# stamp-fixed-mk-4_2.net
KiCad netlist of a schematic drawn in EAGLE
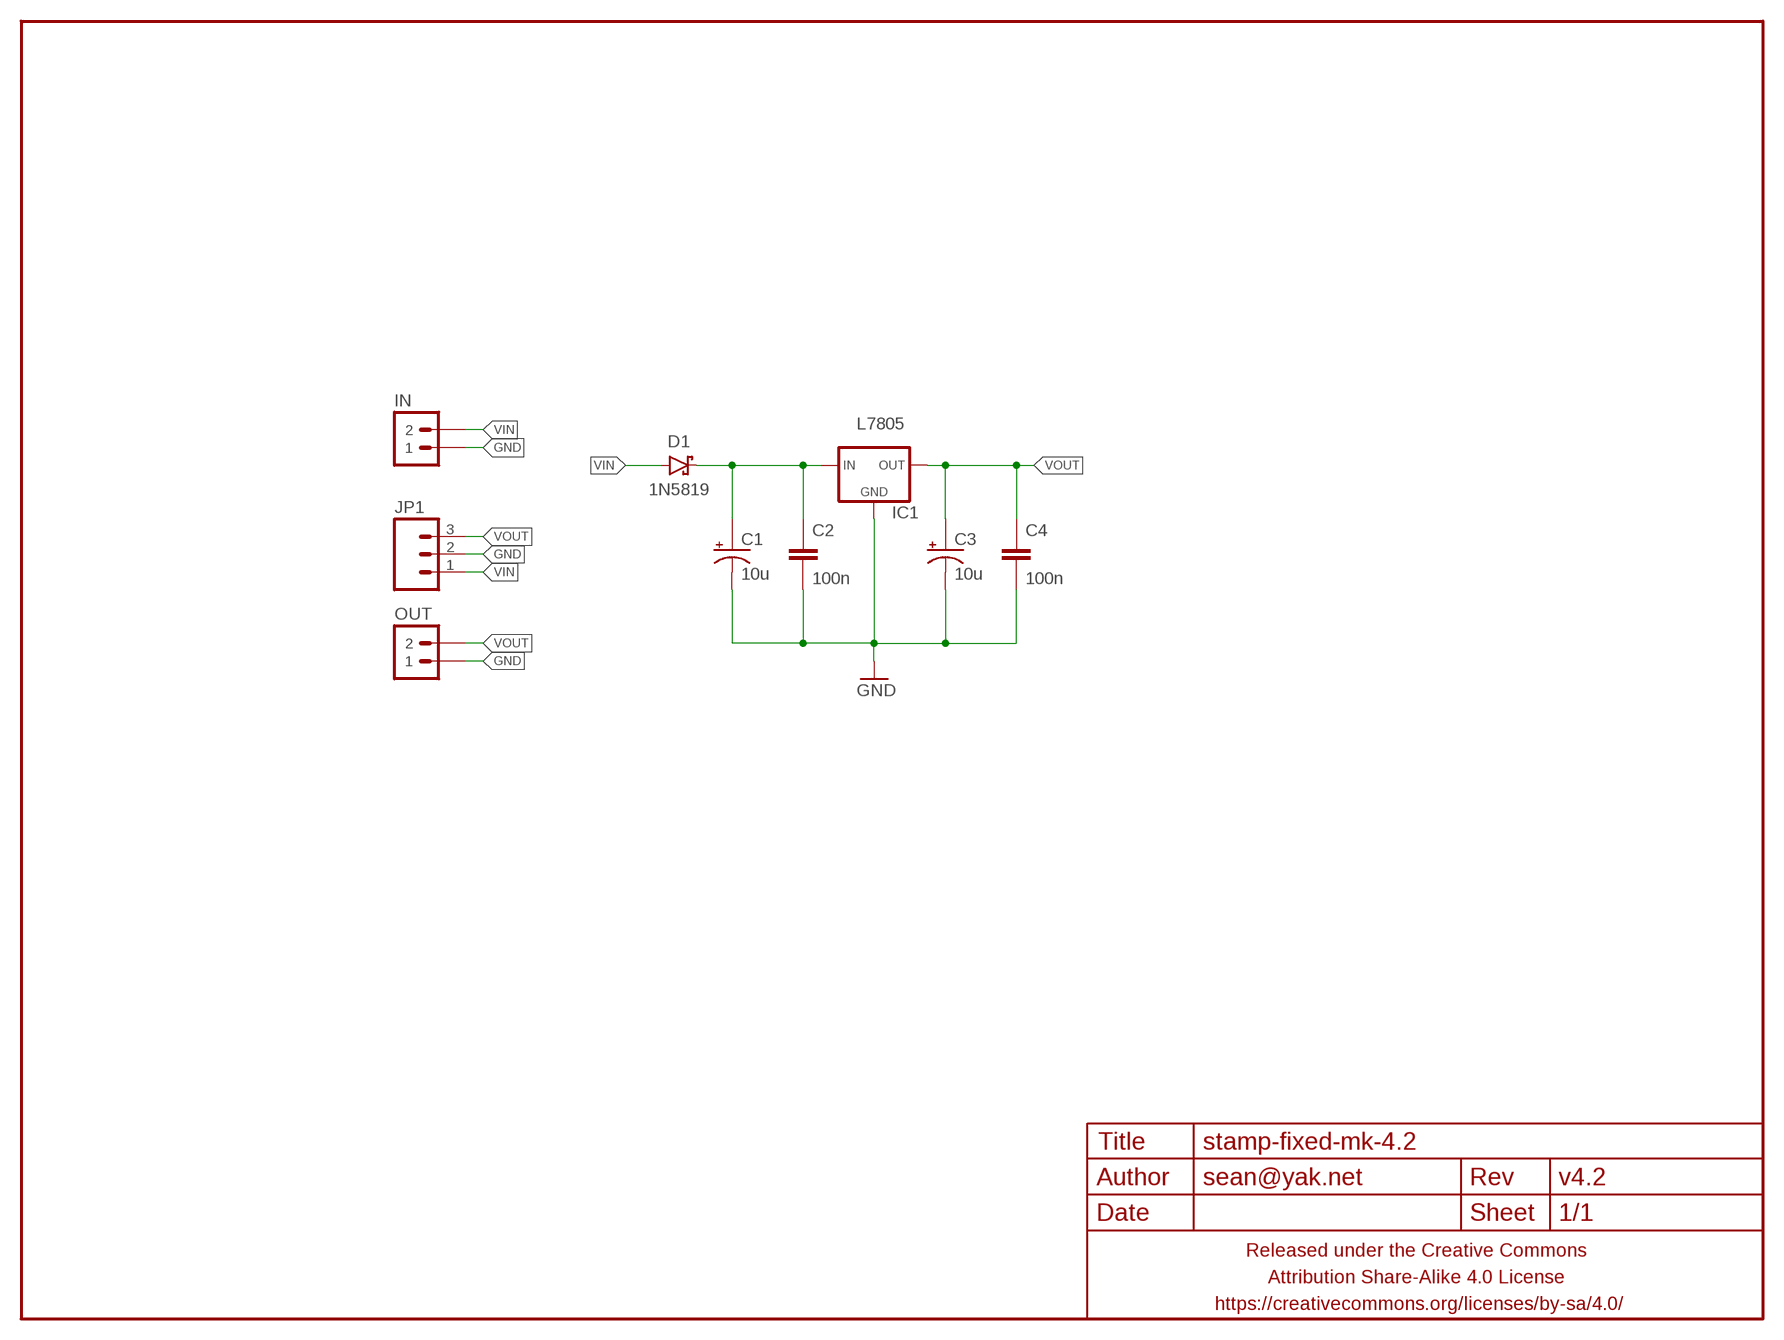
[diagram p0: schematic, sheet 1]

(export (version "E")
  (design (tool "Eeschema 10.0.6"))
  (components
    (comp (ref "C1")
      (value "10u")
      (footprint "eagle-import:E2,5-5")
      (libsource (lib "eagle-import") (part "CAPACITOR-POLARIZEDE2.5-5"))
    )
    (comp (ref "C2")
      (value "100n")
      (footprint "eagle-import:C025-024X044")
      (libsource (lib "eagle-import") (part "CAPACITOR-CERAMIC025-024X044"))
    )
    (comp (ref "C3")
      (value "10u")
      (footprint "eagle-import:E2,5-5")
      (libsource (lib "eagle-import") (part "CAPACITOR-POLARIZEDE2.5-5"))
    )
    (comp (ref "C4")
      (value "100n")
      (footprint "eagle-import:C025-024X044")
      (libsource (lib "eagle-import") (part "CAPACITOR-CERAMIC025-024X044"))
    )
    (comp (ref "D1")
      (value "1N5819")
      (footprint "eagle-import:DIODE-SCHOTTKY-10.16MM")
      (libsource (lib "eagle-import") (part "DIODE-SCHOTTKYPTH-10.16MM"))
    )
    (comp (ref "FRAME1")
      (value "FRAME-LETTERNO_PACKAGE")
      (footprint "eagle-import:DUMMY")
      (fields (field (name "DESIGNER") "sean@yak.net") (field (name "VERSION") "v4.2"))
      (libsource (lib "eagle-import") (part "FRAME-LETTERNO_PACKAGE"))
    )
    (comp (ref "IC1")
      (value "L7805")
      (footprint "eagle-import:TO220-IGO-THERMPAD")
      (libsource (lib "eagle-import") (part "V_REG_78XXTO-220-THERMPAD"))
    )
    (comp (ref "IN")
      (value "M02PTH-CENTERED-R+")
      (footprint "eagle-import:1X02-CENTER-R+")
      (libsource (lib "eagle-import") (part "M02PTH-CENTERED-R+"))
    )
    (comp (ref "JP1")
      (value "M03PTH-CENTERED")
      (footprint "eagle-import:1X03-CENTERED")
      (libsource (lib "eagle-import") (part "M03PTH-CENTERED"))
    )
    (comp (ref "OUT")
      (value "M02PTH-CENTERED-R+")
      (footprint "eagle-import:1X02-CENTER-R+")
      (libsource (lib "eagle-import") (part "M02PTH-CENTERED-R+"))
    )
  )
  (nets
    (net (code "1") (name "GND") (class "Default")
      (node (ref "C1") (pin "-") (pinfunction "-_-") (pintype "passive"))
      (node (ref "C2") (pin "2") (pinfunction "2_2") (pintype "passive"))
      (node (ref "C3") (pin "-") (pinfunction "-_-") (pintype "passive"))
      (node (ref "C4") (pin "2") (pinfunction "2_2") (pintype "passive"))
      (node (ref "IC1") (pin "4") (pinfunction "GND_4") (pintype "bidirectional"))
      (node (ref "IC1") (pin "GND") (pinfunction "GND_GND") (pintype "bidirectional"))
      (node (ref "IN") (pin "1") (pinfunction "1_1") (pintype "passive"))
      (node (ref "JP1") (pin "2") (pinfunction "2_2") (pintype "passive"))
      (node (ref "OUT") (pin "1") (pinfunction "1_1") (pintype "passive"))
    )
    (net (code "2") (name "Net-(C1-Pad+)") (class "Default")
      (node (ref "C1") (pin "+") (pinfunction "+_+") (pintype "passive"))
      (node (ref "C2") (pin "1") (pinfunction "1_1") (pintype "passive"))
      (node (ref "D1") (pin "C") (pinfunction "C_C") (pintype "passive"))
      (node (ref "IC1") (pin "IN") (pinfunction "IN_IN") (pintype "bidirectional"))
    )
    (net (code "3") (name "VIN") (class "Default")
      (node (ref "D1") (pin "A") (pinfunction "A_A") (pintype "passive"))
      (node (ref "IN") (pin "2") (pinfunction "2_2") (pintype "passive"))
      (node (ref "JP1") (pin "1") (pinfunction "1_1") (pintype "passive"))
    )
    (net (code "4") (name "VOUT") (class "Default")
      (node (ref "C3") (pin "+") (pinfunction "+_+") (pintype "passive"))
      (node (ref "C4") (pin "1") (pinfunction "1_1") (pintype "passive"))
      (node (ref "IC1") (pin "OUT") (pinfunction "OUT_OUT") (pintype "bidirectional"))
      (node (ref "JP1") (pin "3") (pinfunction "3_3") (pintype "passive"))
      (node (ref "OUT") (pin "2") (pinfunction "2_2") (pintype "passive"))
    )
  )
)
